# macropad.net
KiCad netlist of a schematic drawn in EAGLE
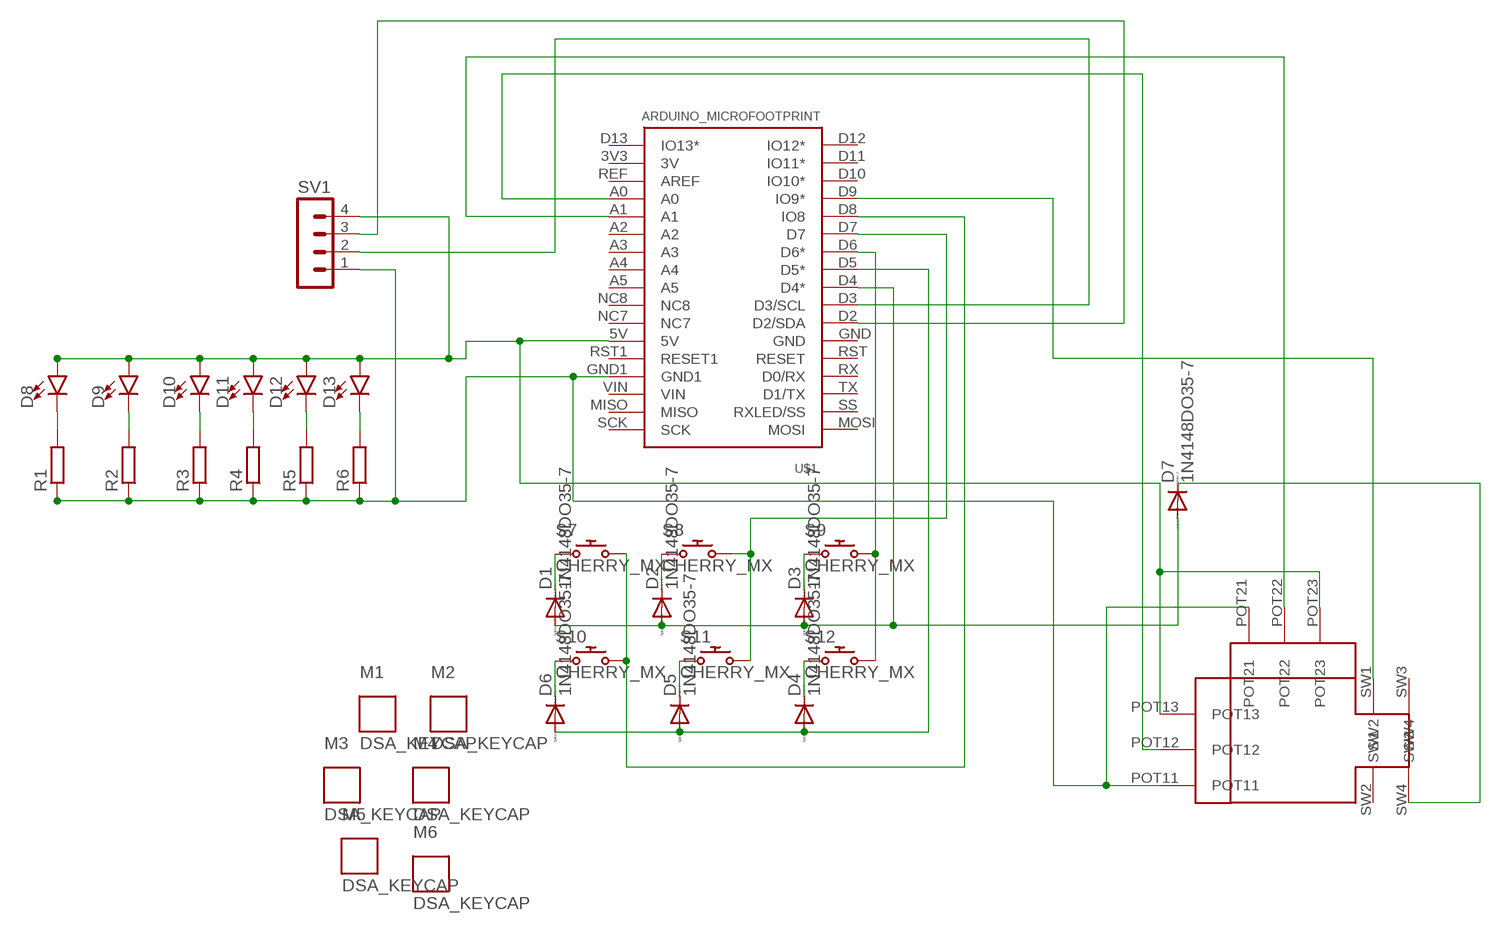
[diagram p0: schematic, sheet 1]

(export (version "E")
  (design (tool "Eeschema 10.0.6"))
  (components
    (comp (ref "D1")
      (value "1N4148DO35-7")
      (footprint "eagle-import:DO35-7")
      (libsource (lib "eagle-import") (part "1N4148DO35-7"))
    )
    (comp (ref "D2")
      (value "1N4148DO35-7")
      (footprint "eagle-import:DO35-7")
      (libsource (lib "eagle-import") (part "1N4148DO35-7"))
    )
    (comp (ref "D3")
      (value "1N4148DO35-7")
      (footprint "eagle-import:DO35-7")
      (libsource (lib "eagle-import") (part "1N4148DO35-7"))
    )
    (comp (ref "D4")
      (value "1N4148DO35-7")
      (footprint "eagle-import:DO35-7")
      (libsource (lib "eagle-import") (part "1N4148DO35-7"))
    )
    (comp (ref "D5")
      (value "1N4148DO35-7")
      (footprint "eagle-import:DO35-7")
      (libsource (lib "eagle-import") (part "1N4148DO35-7"))
    )
    (comp (ref "D6")
      (value "1N4148DO35-7")
      (footprint "eagle-import:DO35-7")
      (libsource (lib "eagle-import") (part "1N4148DO35-7"))
    )
    (comp (ref "D7")
      (value "1N4148DO35-7")
      (footprint "eagle-import:DO35-7")
      (libsource (lib "eagle-import") (part "1N4148DO35-7"))
    )
    (comp (ref "D8")
      (value "LED-3MM-NO_SILK")
      (footprint "eagle-import:LED_3MM-NS")
      (libsource (lib "eagle-import") (part "LED-3MM-NO_SILK"))
    )
    (comp (ref "D9")
      (value "LED-3MM-NO_SILK")
      (footprint "eagle-import:LED_3MM-NS")
      (libsource (lib "eagle-import") (part "LED-3MM-NO_SILK"))
    )
    (comp (ref "D10")
      (value "LED-3MM-NO_SILK")
      (footprint "eagle-import:LED_3MM-NS")
      (libsource (lib "eagle-import") (part "LED-3MM-NO_SILK"))
    )
    (comp (ref "D11")
      (value "LED-3MM-NO_SILK")
      (footprint "eagle-import:LED_3MM-NS")
      (libsource (lib "eagle-import") (part "LED-3MM-NO_SILK"))
    )
    (comp (ref "D12")
      (value "LED-3MM-NO_SILK")
      (footprint "eagle-import:LED_3MM-NS")
      (libsource (lib "eagle-import") (part "LED-3MM-NO_SILK"))
    )
    (comp (ref "D13")
      (value "LED-3MM-NO_SILK")
      (footprint "eagle-import:LED_3MM-NS")
      (libsource (lib "eagle-import") (part "LED-3MM-NO_SILK"))
    )
    (comp (ref "M1")
      (value "DSA_KEYCAP")
      (footprint "eagle-import:DSA_KEYCAP")
      (libsource (lib "eagle-import") (part "DSA_KEYCAP"))
    )
    (comp (ref "M2")
      (value "DSA_KEYCAP")
      (footprint "eagle-import:DSA_KEYCAP")
      (libsource (lib "eagle-import") (part "DSA_KEYCAP"))
    )
    (comp (ref "M3")
      (value "DSA_KEYCAP")
      (footprint "eagle-import:DSA_KEYCAP")
      (libsource (lib "eagle-import") (part "DSA_KEYCAP"))
    )
    (comp (ref "M4")
      (value "DSA_KEYCAP")
      (footprint "eagle-import:DSA_KEYCAP")
      (libsource (lib "eagle-import") (part "DSA_KEYCAP"))
    )
    (comp (ref "M5")
      (value "DSA_KEYCAP")
      (footprint "eagle-import:DSA_KEYCAP")
      (libsource (lib "eagle-import") (part "DSA_KEYCAP"))
    )
    (comp (ref "M6")
      (value "DSA_KEYCAP")
      (footprint "eagle-import:DSA_KEYCAP")
      (libsource (lib "eagle-import") (part "DSA_KEYCAP"))
    )
    (comp (ref "R1")
      (value "R-EU_0204/7")
      (footprint "eagle-import:0204_7")
      (libsource (lib "eagle-import") (part "R-EU_0204/7"))
    )
    (comp (ref "R2")
      (value "R-EU_0204/7")
      (footprint "eagle-import:0204_7")
      (libsource (lib "eagle-import") (part "R-EU_0204/7"))
    )
    (comp (ref "R3")
      (value "R-EU_0204/7")
      (footprint "eagle-import:0204_7")
      (libsource (lib "eagle-import") (part "R-EU_0204/7"))
    )
    (comp (ref "R4")
      (value "R-EU_0204/7")
      (footprint "eagle-import:0204_7")
      (libsource (lib "eagle-import") (part "R-EU_0204/7"))
    )
    (comp (ref "R5")
      (value "R-EU_0204/7")
      (footprint "eagle-import:0204_7")
      (libsource (lib "eagle-import") (part "R-EU_0204/7"))
    )
    (comp (ref "R6")
      (value "R-EU_0204/7")
      (footprint "eagle-import:0204_7")
      (libsource (lib "eagle-import") (part "R-EU_0204/7"))
    )
    (comp (ref "S7")
      (value "CHERRY_MX")
      (footprint "eagle-import:CHERRY_MX")
      (libsource (lib "eagle-import") (part "CHERRY_MX"))
    )
    (comp (ref "S8")
      (value "CHERRY_MX")
      (footprint "eagle-import:CHERRY_MX")
      (libsource (lib "eagle-import") (part "CHERRY_MX"))
    )
    (comp (ref "S9")
      (value "CHERRY_MX")
      (footprint "eagle-import:CHERRY_MX")
      (libsource (lib "eagle-import") (part "CHERRY_MX"))
    )
    (comp (ref "S10")
      (value "CHERRY_MX")
      (footprint "eagle-import:CHERRY_MX")
      (libsource (lib "eagle-import") (part "CHERRY_MX"))
    )
    (comp (ref "S11")
      (value "CHERRY_MX")
      (footprint "eagle-import:CHERRY_MX")
      (libsource (lib "eagle-import") (part "CHERRY_MX"))
    )
    (comp (ref "S12")
      (value "CHERRY_MX")
      (footprint "eagle-import:CHERRY_MX")
      (libsource (lib "eagle-import") (part "CHERRY_MX"))
    )
    (comp (ref "SV1")
      (value "MA04-1")
      (footprint "eagle-import:MA04-1")
      (libsource (lib "eagle-import") (part "MA04-1"))
    )
    (comp (ref "U$1")
      (value "ARDUINO_MICROFOOTPRINT")
      (footprint "eagle-import:ARDUINO-MICRO")
      (libsource (lib "eagle-import") (part "ARDUINO_MICROFOOTPRINT"))
    )
    (comp (ref "U$2")
      (value "JOYSTICK")
      (footprint "eagle-import:JOYSTICKONE")
      (libsource (lib "eagle-import") (part "JOYSTICK"))
    )
  )
  (nets
    (net (code "1") (name "Net-(D7-PadC)") (class "Default")
      (node (ref "D7") (pin "C") (pinfunction "C_C") (pintype "passive"))
      (node (ref "U$2") (pin "SW4") (pinfunction "SW4_SW4") (pintype "bidirectional"))
    )
    (net (code "2") (name "Net-(D8-C)") (class "Default")
      (node (ref "D8") (pin "K") (pinfunction "C_K") (pintype "passive"))
      (node (ref "R1") (pin "2") (pinfunction "2_2") (pintype "passive"))
    )
    (net (code "3") (name "Net-(D9-C)") (class "Default")
      (node (ref "D9") (pin "K") (pinfunction "C_K") (pintype "passive"))
      (node (ref "R2") (pin "2") (pinfunction "2_2") (pintype "passive"))
    )
    (net (code "4") (name "Net-(D10-C)") (class "Default")
      (node (ref "D10") (pin "K") (pinfunction "C_K") (pintype "passive"))
      (node (ref "R3") (pin "2") (pinfunction "2_2") (pintype "passive"))
    )
    (net (code "5") (name "Net-(D10-PadA)") (class "Default")
      (node (ref "D10") (pin "A") (pinfunction "A_A") (pintype "passive"))
      (node (ref "D11") (pin "A") (pinfunction "A_A") (pintype "passive"))
      (node (ref "D12") (pin "A") (pinfunction "A_A") (pintype "passive"))
      (node (ref "D13") (pin "A") (pinfunction "A_A") (pintype "passive"))
      (node (ref "D8") (pin "A") (pinfunction "A_A") (pintype "passive"))
      (node (ref "D9") (pin "A") (pinfunction "A_A") (pintype "passive"))
      (node (ref "SV1") (pin "4") (pinfunction "4_4") (pintype "passive"))
      (node (ref "U$1") (pin "5V") (pinfunction "5V_5V") (pintype "bidirectional"))
      (node (ref "U$2") (pin "POT13") (pinfunction "POT13_POT13") (pintype "bidirectional"))
      (node (ref "U$2") (pin "POT23") (pinfunction "POT23_POT23") (pintype "bidirectional"))
    )
    (net (code "6") (name "Net-(D11-C)") (class "Default")
      (node (ref "D11") (pin "K") (pinfunction "C_K") (pintype "passive"))
      (node (ref "R4") (pin "2") (pinfunction "2_2") (pintype "passive"))
    )
    (net (code "7") (name "Net-(D12-C)") (class "Default")
      (node (ref "D12") (pin "K") (pinfunction "C_K") (pintype "passive"))
      (node (ref "R5") (pin "2") (pinfunction "2_2") (pintype "passive"))
    )
    (net (code "8") (name "Net-(D13-C)") (class "Default")
      (node (ref "D13") (pin "K") (pinfunction "C_K") (pintype "passive"))
      (node (ref "R6") (pin "2") (pinfunction "2_2") (pintype "passive"))
    )
    (net (code "9") (name "Net-(R1-Pad1)") (class "Default")
      (node (ref "R1") (pin "1") (pinfunction "1_1") (pintype "passive"))
      (node (ref "R2") (pin "1") (pinfunction "1_1") (pintype "passive"))
      (node (ref "R3") (pin "1") (pinfunction "1_1") (pintype "passive"))
      (node (ref "R4") (pin "1") (pinfunction "1_1") (pintype "passive"))
      (node (ref "R5") (pin "1") (pinfunction "1_1") (pintype "passive"))
      (node (ref "R6") (pin "1") (pinfunction "1_1") (pintype "passive"))
      (node (ref "SV1") (pin "1") (pinfunction "1_1") (pintype "passive"))
      (node (ref "U$1") (pin "GND1") (pinfunction "GND1_GND1") (pintype "bidirectional"))
      (node (ref "U$2") (pin "POT11") (pinfunction "POT11_POT11") (pintype "bidirectional"))
      (node (ref "U$2") (pin "POT21") (pinfunction "POT21_POT21") (pintype "bidirectional"))
    )
    (net (code "10") (name "Net-(S7-1)") (class "Default")
      (node (ref "D1") (pin "C") (pinfunction "C_C") (pintype "passive"))
      (node (ref "S7") (pin "S1") (pinfunction "1_S1") (pintype "passive"))
    )
    (net (code "11") (name "Net-(S8-1)") (class "Default")
      (node (ref "D2") (pin "C") (pinfunction "C_C") (pintype "passive"))
      (node (ref "S8") (pin "S1") (pinfunction "1_S1") (pintype "passive"))
    )
    (net (code "12") (name "Net-(S9-1)") (class "Default")
      (node (ref "D3") (pin "C") (pinfunction "C_C") (pintype "passive"))
      (node (ref "S9") (pin "S1") (pinfunction "1_S1") (pintype "passive"))
    )
    (net (code "13") (name "Net-(S10-1)") (class "Default")
      (node (ref "D6") (pin "C") (pinfunction "C_C") (pintype "passive"))
      (node (ref "S10") (pin "S1") (pinfunction "1_S1") (pintype "passive"))
    )
    (net (code "14") (name "Net-(S10-2)") (class "Default")
      (node (ref "S10") (pin "S2") (pinfunction "2_S2") (pintype "passive"))
      (node (ref "S7") (pin "S2") (pinfunction "2_S2") (pintype "passive"))
      (node (ref "U$1") (pin "D8") (pinfunction "IO8_D8") (pintype "bidirectional"))
    )
    (net (code "15") (name "Net-(S11-1)") (class "Default")
      (node (ref "D5") (pin "C") (pinfunction "C_C") (pintype "passive"))
      (node (ref "S11") (pin "S1") (pinfunction "1_S1") (pintype "passive"))
    )
    (net (code "16") (name "Net-(S11-2)") (class "Default")
      (node (ref "S11") (pin "S2") (pinfunction "2_S2") (pintype "passive"))
      (node (ref "S8") (pin "S2") (pinfunction "2_S2") (pintype "passive"))
      (node (ref "U$1") (pin "D7") (pinfunction "D7_D7") (pintype "bidirectional"))
    )
    (net (code "17") (name "Net-(S12-1)") (class "Default")
      (node (ref "D4") (pin "C") (pinfunction "C_C") (pintype "passive"))
      (node (ref "S12") (pin "S1") (pinfunction "1_S1") (pintype "passive"))
    )
    (net (code "18") (name "Net-(S12-2)") (class "Default")
      (node (ref "S12") (pin "S2") (pinfunction "2_S2") (pintype "passive"))
      (node (ref "S9") (pin "S2") (pinfunction "2_S2") (pintype "passive"))
      (node (ref "U$1") (pin "D6") (pinfunction "D6*_D6") (pintype "bidirectional"))
    )
    (net (code "19") (name "Net-(U$1-D2{slash}SDA)") (class "Default")
      (node (ref "SV1") (pin "3") (pinfunction "3_3") (pintype "passive"))
      (node (ref "U$1") (pin "D2") (pinfunction "D2/SDA_D2") (pintype "bidirectional"))
    )
    (net (code "20") (name "Net-(U$1-D3{slash}SCL)") (class "Default")
      (node (ref "SV1") (pin "2") (pinfunction "2_2") (pintype "passive"))
      (node (ref "U$1") (pin "D3") (pinfunction "D3/SCL_D3") (pintype "bidirectional"))
    )
    (net (code "21") (name "Net-(U$1-D4*)") (class "Default")
      (node (ref "D1") (pin "A") (pinfunction "A_A") (pintype "passive"))
      (node (ref "D2") (pin "A") (pinfunction "A_A") (pintype "passive"))
      (node (ref "D3") (pin "A") (pinfunction "A_A") (pintype "passive"))
      (node (ref "D7") (pin "A") (pinfunction "A_A") (pintype "passive"))
      (node (ref "U$1") (pin "D4") (pinfunction "D4*_D4") (pintype "bidirectional"))
    )
    (net (code "22") (name "Net-(U$1-D5*)") (class "Default")
      (node (ref "D4") (pin "A") (pinfunction "A_A") (pintype "passive"))
      (node (ref "D5") (pin "A") (pinfunction "A_A") (pintype "passive"))
      (node (ref "D6") (pin "A") (pinfunction "A_A") (pintype "passive"))
      (node (ref "U$1") (pin "D5") (pinfunction "D5*_D5") (pintype "bidirectional"))
    )
    (net (code "23") (name "Net-(U$1-IO9*)") (class "Default")
      (node (ref "U$1") (pin "D9") (pinfunction "IO9*_D9") (pintype "bidirectional"))
      (node (ref "U$2") (pin "SW1") (pinfunction "SW1_SW1") (pintype "bidirectional"))
    )
    (net (code "24") (name "Net-(U$1-PadA0)") (class "Default")
      (node (ref "U$1") (pin "A0") (pinfunction "A0_A0") (pintype "bidirectional"))
      (node (ref "U$2") (pin "POT12") (pinfunction "POT12_POT12") (pintype "bidirectional"))
    )
    (net (code "25") (name "Net-(U$1-PadA1)") (class "Default")
      (node (ref "U$1") (pin "A1") (pinfunction "A1_A1") (pintype "bidirectional"))
      (node (ref "U$2") (pin "POT22") (pinfunction "POT22_POT22") (pintype "bidirectional"))
    )
    (net (code "26") (name "unconnected-(U$1-3V-Pad3V3)") (class "Default")
      (node (ref "U$1") (pin "3V3") (pinfunction "3V_3V3") (pintype "bidirectional"))
    )
    (net (code "27") (name "unconnected-(U$1-AREF-PadREF)") (class "Default")
      (node (ref "U$1") (pin "REF") (pinfunction "AREF_REF") (pintype "bidirectional"))
    )
    (net (code "28") (name "unconnected-(U$1-D0{slash}RX-PadRX)") (class "Default")
      (node (ref "U$1") (pin "RX") (pinfunction "D0/RX_RX") (pintype "bidirectional"))
    )
    (net (code "29") (name "unconnected-(U$1-D1{slash}TX-PadTX)") (class "Default")
      (node (ref "U$1") (pin "TX") (pinfunction "D1/TX_TX") (pintype "bidirectional"))
    )
    (net (code "30") (name "unconnected-(U$1-IO10*-PadD10)") (class "Default")
      (node (ref "U$1") (pin "D10") (pinfunction "IO10*_D10") (pintype "bidirectional"))
    )
    (net (code "31") (name "unconnected-(U$1-IO11*-PadD11)") (class "Default")
      (node (ref "U$1") (pin "D11") (pinfunction "IO11*_D11") (pintype "bidirectional"))
    )
    (net (code "32") (name "unconnected-(U$1-IO12*-PadD12)") (class "Default")
      (node (ref "U$1") (pin "D12") (pinfunction "IO12*_D12") (pintype "bidirectional"))
    )
    (net (code "33") (name "unconnected-(U$1-IO13*-PadD13)") (class "Default")
      (node (ref "U$1") (pin "D13") (pinfunction "IO13*_D13") (pintype "bidirectional"))
    )
    (net (code "34") (name "unconnected-(U$1-PadA2)") (class "Default")
      (node (ref "U$1") (pin "A2") (pinfunction "A2_A2") (pintype "bidirectional"))
    )
    (net (code "35") (name "unconnected-(U$1-PadA3)") (class "Default")
      (node (ref "U$1") (pin "A3") (pinfunction "A3_A3") (pintype "bidirectional"))
    )
    (net (code "36") (name "unconnected-(U$1-PadA4)") (class "Default")
      (node (ref "U$1") (pin "A4") (pinfunction "A4_A4") (pintype "bidirectional"))
    )
    (net (code "37") (name "unconnected-(U$1-PadA5)") (class "Default")
      (node (ref "U$1") (pin "A5") (pinfunction "A5_A5") (pintype "bidirectional"))
    )
    (net (code "38") (name "unconnected-(U$1-PadGND)") (class "Default")
      (node (ref "U$1") (pin "GND") (pinfunction "GND_GND") (pintype "bidirectional"))
    )
    (net (code "39") (name "unconnected-(U$1-PadMISO)") (class "Default")
      (node (ref "U$1") (pin "MISO") (pinfunction "MISO_MISO") (pintype "bidirectional"))
    )
    (net (code "40") (name "unconnected-(U$1-PadMOSI)") (class "Default")
      (node (ref "U$1") (pin "MOSI") (pinfunction "MOSI_MOSI") (pintype "bidirectional"))
    )
    (net (code "41") (name "unconnected-(U$1-PadNC7)") (class "Default")
      (node (ref "U$1") (pin "NC7") (pinfunction "NC7_NC7") (pintype "bidirectional"))
    )
    (net (code "42") (name "unconnected-(U$1-PadNC8)") (class "Default")
      (node (ref "U$1") (pin "NC8") (pinfunction "NC8_NC8") (pintype "bidirectional"))
    )
    (net (code "43") (name "unconnected-(U$1-PadSCK)") (class "Default")
      (node (ref "U$1") (pin "SCK") (pinfunction "SCK_SCK") (pintype "bidirectional"))
    )
    (net (code "44") (name "unconnected-(U$1-PadVIN)") (class "Default")
      (node (ref "U$1") (pin "VIN") (pinfunction "VIN_VIN") (pintype "bidirectional"))
    )
    (net (code "45") (name "unconnected-(U$1-RESET-PadRST)") (class "Default")
      (node (ref "U$1") (pin "RST") (pinfunction "RESET_RST") (pintype "bidirectional"))
    )
    (net (code "46") (name "unconnected-(U$1-RESET1-PadRST1)") (class "Default")
      (node (ref "U$1") (pin "RST1") (pinfunction "RESET1_RST1") (pintype "bidirectional"))
    )
    (net (code "47") (name "unconnected-(U$1-RXLED{slash}SS-PadSS)") (class "Default")
      (node (ref "U$1") (pin "SS") (pinfunction "RXLED/SS_SS") (pintype "bidirectional"))
    )
    (net (code "48") (name "unconnected-(U$2-PadSW2)") (class "Default")
      (node (ref "U$2") (pin "SW2") (pinfunction "SW2_SW2") (pintype "bidirectional"))
    )
    (net (code "49") (name "unconnected-(U$2-PadSW3)") (class "Default")
      (node (ref "U$2") (pin "SW3") (pinfunction "SW3_SW3") (pintype "bidirectional"))
    )
  )
)
